# esp32_pwr.net
KiCad netlist of a schematic drawn in EAGLE
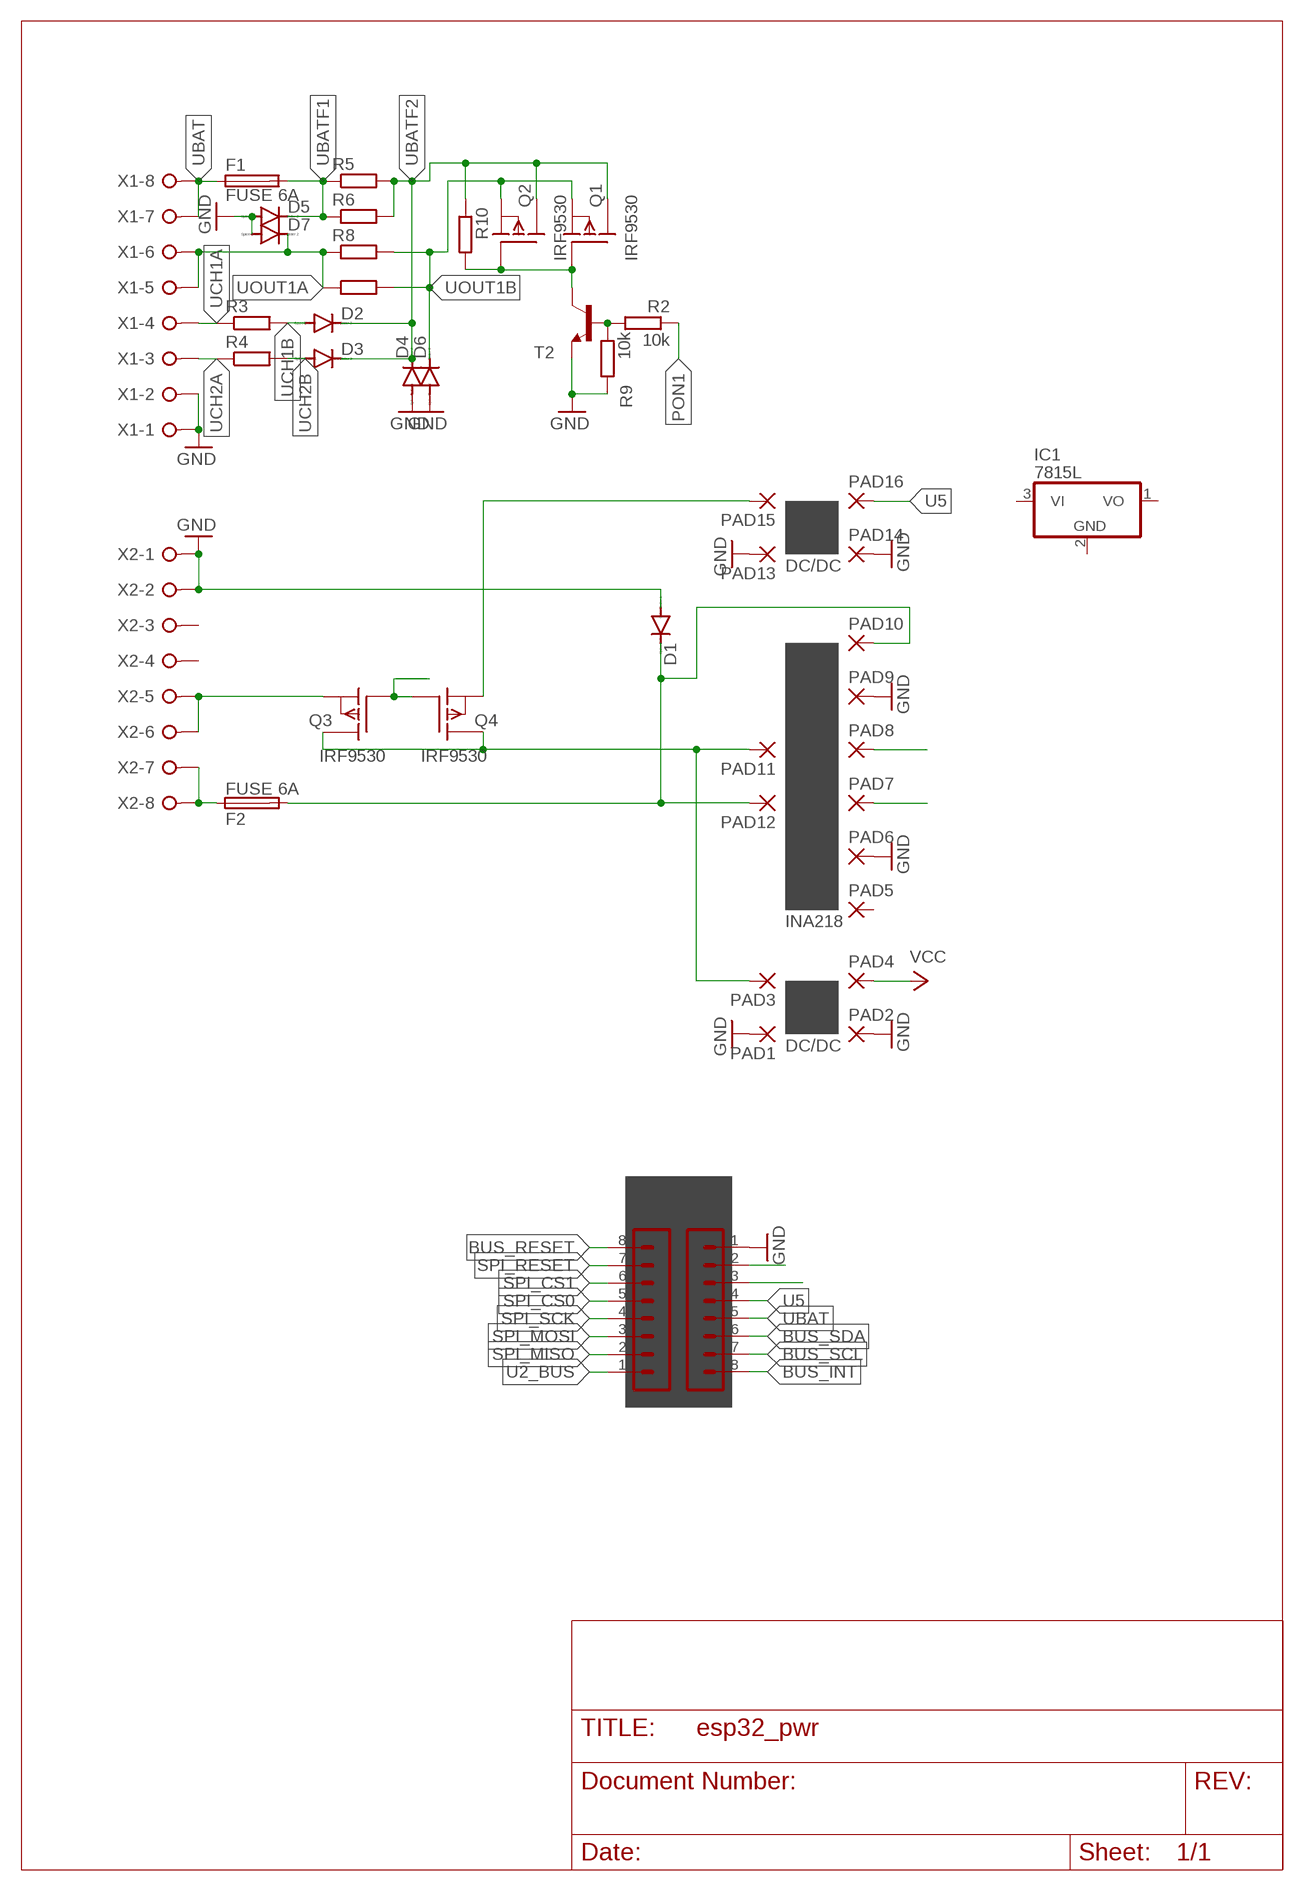
[diagram p0: schematic, sheet 1]

(export (version "E")
  (design (tool "Eeschema 10.0.6"))
  (components
    (comp (ref "D1")
      (value "DIODE-MELF-MLL41")
      (footprint "eagle-import:MELF-MLL41")
      (libsource (lib "eagle-import") (part "DIODE-MELF-MLL41"))
    )
    (comp (ref "D2")
      (value "DIODE-MELF-MLL41")
      (footprint "eagle-import:MELF-MLL41")
      (libsource (lib "eagle-import") (part "DIODE-MELF-MLL41"))
    )
    (comp (ref "D3")
      (value "DIODE-MELF-MLL41")
      (footprint "eagle-import:MELF-MLL41")
      (libsource (lib "eagle-import") (part "DIODE-MELF-MLL41"))
    )
    (comp (ref "D4")
      (value "DIODE-MELF-MLL41")
      (footprint "eagle-import:MELF-MLL41")
      (libsource (lib "eagle-import") (part "DIODE-MELF-MLL41"))
    )
    (comp (ref "D5")
      (value "DIODE-MELF-MLL41")
      (footprint "eagle-import:MELF-MLL41")
      (libsource (lib "eagle-import") (part "DIODE-MELF-MLL41"))
    )
    (comp (ref "D6")
      (value "DIODE-MELF-MLL41")
      (footprint "eagle-import:MELF-MLL41")
      (libsource (lib "eagle-import") (part "DIODE-MELF-MLL41"))
    )
    (comp (ref "D7")
      (value "DIODE-MELF-MLL41")
      (footprint "eagle-import:MELF-MLL41")
      (libsource (lib "eagle-import") (part "DIODE-MELF-MLL41"))
    )
    (comp (ref "F1")
      (value "FUSE 6A")
      (footprint "eagle-import:SH22,5A")
      (libsource (lib "eagle-import") (part "FUSESH22,5A"))
    )
    (comp (ref "F2")
      (value "FUSE 6A")
      (footprint "eagle-import:SH22,5A")
      (libsource (lib "eagle-import") (part "FUSESH22,5A"))
    )
    (comp (ref "IC1")
      (value "7815L")
      (footprint "eagle-import:TO92")
      (libsource (lib "eagle-import") (part "78L15"))
    )
    (comp (ref "L")
      (value "MA08-1")
      (footprint "eagle-import:MA08-1")
      (libsource (lib "eagle-import") (part "MA08-1"))
    )
    (comp (ref "PAD1")
      (value "2,15/1,0")
      (footprint "eagle-import:2,15_1,0")
      (libsource (lib "eagle-import") (part "2,15/1,0"))
    )
    (comp (ref "PAD2")
      (value "2,15/1,0")
      (footprint "eagle-import:2,15_1,0")
      (libsource (lib "eagle-import") (part "2,15/1,0"))
    )
    (comp (ref "PAD3")
      (value "2,15/1,0")
      (footprint "eagle-import:2,15_1,0")
      (libsource (lib "eagle-import") (part "2,15/1,0"))
    )
    (comp (ref "PAD4")
      (value "2,15/1,0")
      (footprint "eagle-import:2,15_1,0")
      (libsource (lib "eagle-import") (part "2,15/1,0"))
    )
    (comp (ref "PAD5")
      (value "2,15/1,0")
      (footprint "eagle-import:2,15_1,0")
      (libsource (lib "eagle-import") (part "2,15/1,0"))
    )
    (comp (ref "PAD6")
      (value "2,15/1,0")
      (footprint "eagle-import:2,15_1,0")
      (libsource (lib "eagle-import") (part "2,15/1,0"))
    )
    (comp (ref "PAD7")
      (value "2,15/1,0")
      (footprint "eagle-import:2,15_1,0")
      (libsource (lib "eagle-import") (part "2,15/1,0"))
    )
    (comp (ref "PAD8")
      (value "2,15/1,0")
      (footprint "eagle-import:2,15_1,0")
      (libsource (lib "eagle-import") (part "2,15/1,0"))
    )
    (comp (ref "PAD9")
      (value "2,15/1,0")
      (footprint "eagle-import:2,15_1,0")
      (libsource (lib "eagle-import") (part "2,15/1,0"))
    )
    (comp (ref "PAD10")
      (value "2,15/1,0")
      (footprint "eagle-import:2,15_1,0")
      (libsource (lib "eagle-import") (part "2,15/1,0"))
    )
    (comp (ref "PAD11")
      (value "2,15/1,0")
      (footprint "eagle-import:2,15_1,0")
      (libsource (lib "eagle-import") (part "2,15/1,0"))
    )
    (comp (ref "PAD12")
      (value "2,15/1,0")
      (footprint "eagle-import:2,15_1,0")
      (libsource (lib "eagle-import") (part "2,15/1,0"))
    )
    (comp (ref "PAD13")
      (value "2,15/1,0")
      (footprint "eagle-import:2,15_1,0")
      (libsource (lib "eagle-import") (part "2,15/1,0"))
    )
    (comp (ref "PAD14")
      (value "2,15/1,0")
      (footprint "eagle-import:2,15_1,0")
      (libsource (lib "eagle-import") (part "2,15/1,0"))
    )
    (comp (ref "PAD15")
      (value "2,15/1,0")
      (footprint "eagle-import:2,15_1,0")
      (libsource (lib "eagle-import") (part "2,15/1,0"))
    )
    (comp (ref "PAD16")
      (value "2,15/1,0")
      (footprint "eagle-import:2,15_1,0")
      (libsource (lib "eagle-import") (part "2,15/1,0"))
    )
    (comp (ref "Q1")
      (value "IRF9530")
      (footprint "eagle-import:TO220")
      (libsource (lib "eagle-import") (part "IRF9530"))
    )
    (comp (ref "Q2")
      (value "IRF9530")
      (footprint "eagle-import:TO220")
      (libsource (lib "eagle-import") (part "IRF9530"))
    )
    (comp (ref "Q3")
      (value "IRF9530")
      (footprint "eagle-import:TO220")
      (libsource (lib "eagle-import") (part "IRF9530"))
    )
    (comp (ref "Q4")
      (value "IRF9530")
      (footprint "eagle-import:TO220")
      (libsource (lib "eagle-import") (part "IRF9530"))
    )
    (comp (ref "R")
      (value "MA08-1")
      (footprint "eagle-import:MA08-1")
      (libsource (lib "eagle-import") (part "MA08-1"))
    )
    (comp (ref "R2")
      (value "10k")
      (footprint "eagle-import:R0805")
      (libsource (lib "eagle-import") (part "R-EU_R0805"))
    )
    (comp (ref "R3")
      (value "R-EU_R2512")
      (footprint "eagle-import:R2512")
      (libsource (lib "eagle-import") (part "rcl_334_R-EU_R2512"))
    )
    (comp (ref "R4")
      (value "R-EU_R2512")
      (footprint "eagle-import:R2512")
      (libsource (lib "eagle-import") (part "rcl_334_R-EU_R2512"))
    )
    (comp (ref "R5")
      (value "R-EU_R2512")
      (footprint "eagle-import:R2512")
      (libsource (lib "eagle-import") (part "rcl_334_R-EU_R2512"))
    )
    (comp (ref "R6")
      (value "R-EU_R2512")
      (footprint "eagle-import:R2512")
      (libsource (lib "eagle-import") (part "rcl_334_R-EU_R2512"))
    )
    (comp (ref "R7")
      (value "R-EU_R2512")
      (footprint "eagle-import:R2512")
      (libsource (lib "eagle-import") (part "rcl_334_R-EU_R2512"))
    )
    (comp (ref "R8")
      (value "R-EU_R2512")
      (footprint "eagle-import:R2512")
      (libsource (lib "eagle-import") (part "rcl_334_R-EU_R2512"))
    )
    (comp (ref "R9")
      (value "10k")
      (footprint "eagle-import:R0805")
      (libsource (lib "eagle-import") (part "R-EU_R0805"))
    )
    (comp (ref "R10")
      (value "R-EU_R0805")
      (footprint "eagle-import:R0805")
      (libsource (lib "eagle-import") (part "rcl_334_R-EU_R0805"))
    )
    (comp (ref "T2")
      (value "BC817-16-NPN-SOT23-BEC")
      (footprint "eagle-import:SOT23-BEC")
      (libsource (lib "eagle-import") (part "-NPN-SOT23-BECBC817-16"))
    )
    (comp (ref "X1")
      (value "W237-08P")
      (footprint "eagle-import:W237-8P")
      (libsource (lib "eagle-import") (part "W237-08P"))
    )
    (comp (ref "X2")
      (value "W237-08P")
      (footprint "eagle-import:W237-8P")
      (libsource (lib "eagle-import") (part "W237-08P"))
    )
  )
  (nets
    (net (code "1") (name "BUS_INT") (class "Default")
      (node (ref "R") (pin "8") (pinfunction "8_8") (pintype "passive"))
    )
    (net (code "2") (name "BUS_RESET") (class "Default")
      (node (ref "L") (pin "8") (pinfunction "8_8") (pintype "passive"))
    )
    (net (code "3") (name "BUS_SCL") (class "Default")
      (node (ref "R") (pin "7") (pinfunction "7_7") (pintype "passive"))
    )
    (net (code "4") (name "BUS_SDA") (class "Default")
      (node (ref "R") (pin "6") (pinfunction "6_6") (pintype "passive"))
    )
    (net (code "5") (name "GND") (class "Default")
      (node (ref "D1") (pin "A") (pinfunction "A_A") (pintype "passive"))
      (node (ref "D4") (pin "A") (pinfunction "A_A") (pintype "passive"))
      (node (ref "D5") (pin "A") (pinfunction "A_A") (pintype "passive"))
      (node (ref "D6") (pin "A") (pinfunction "A_A") (pintype "passive"))
      (node (ref "D7") (pin "A") (pinfunction "A_A") (pintype "passive"))
      (node (ref "PAD1") (pin "1") (pinfunction "P_1") (pintype "passive"))
      (node (ref "PAD13") (pin "1") (pinfunction "P_1") (pintype "passive"))
      (node (ref "PAD14") (pin "1") (pinfunction "P_1") (pintype "passive"))
      (node (ref "PAD2") (pin "1") (pinfunction "P_1") (pintype "passive"))
      (node (ref "PAD6") (pin "1") (pinfunction "P_1") (pintype "passive"))
      (node (ref "PAD9") (pin "1") (pinfunction "P_1") (pintype "passive"))
      (node (ref "R") (pin "1") (pinfunction "1_1") (pintype "passive"))
      (node (ref "R9") (pin "2") (pinfunction "2_2") (pintype "passive"))
      (node (ref "T2") (pin "E") (pinfunction "E_E") (pintype "passive"))
      (node (ref "X1") (pin "1") (pinfunction "KL_1") (pintype "passive"))
      (node (ref "X1") (pin "2") (pinfunction "KL_2") (pintype "passive"))
      (node (ref "X2") (pin "1") (pinfunction "KL_1") (pintype "passive"))
      (node (ref "X2") (pin "2") (pinfunction "KL_2") (pintype "passive"))
    )
    (net (code "6") (name "Net-(PAD10-P)") (class "Default")
      (node (ref "D1") (pin "C") (pinfunction "C_C") (pintype "passive"))
      (node (ref "F2") (pin "2") (pinfunction "2_2") (pintype "passive"))
      (node (ref "PAD10") (pin "1") (pinfunction "P_1") (pintype "passive"))
      (node (ref "PAD12") (pin "1") (pinfunction "P_1") (pintype "passive"))
    )
    (net (code "7") (name "Net-(PAD11-P)") (class "Default")
      (node (ref "PAD11") (pin "1") (pinfunction "P_1") (pintype "passive"))
      (node (ref "PAD3") (pin "1") (pinfunction "P_1") (pintype "passive"))
      (node (ref "Q3") (pin "2") (pinfunction "D_2") (pintype "passive"))
      (node (ref "Q4") (pin "2") (pinfunction "D_2") (pintype "passive"))
    )
    (net (code "8") (name "Net-(PAD15-P)") (class "Default")
      (node (ref "PAD15") (pin "1") (pinfunction "P_1") (pintype "passive"))
      (node (ref "Q4") (pin "3") (pinfunction "S_3") (pintype "passive"))
    )
    (net (code "9") (name "Net-(Q1-G)") (class "Default")
      (node (ref "Q1") (pin "1") (pinfunction "G_1") (pintype "passive"))
      (node (ref "Q2") (pin "1") (pinfunction "G_1") (pintype "passive"))
      (node (ref "R10") (pin "2") (pinfunction "2_2") (pintype "passive"))
      (node (ref "T2") (pin "C") (pinfunction "C_C") (pintype "passive"))
    )
    (net (code "10") (name "Net-(Q3-G)") (class "Default")
      (node (ref "Q3") (pin "1") (pinfunction "G_1") (pintype "passive"))
      (node (ref "Q4") (pin "1") (pinfunction "G_1") (pintype "passive"))
    )
    (net (code "11") (name "Net-(Q3-S)") (class "Default")
      (node (ref "Q3") (pin "3") (pinfunction "S_3") (pintype "passive"))
      (node (ref "X2") (pin "5") (pinfunction "KL_5") (pintype "passive"))
      (node (ref "X2") (pin "6") (pinfunction "KL_6") (pintype "passive"))
    )
    (net (code "12") (name "Net-(R2-Pad2)") (class "Default")
      (node (ref "R2") (pin "2") (pinfunction "2_2") (pintype "passive"))
      (node (ref "R9") (pin "1") (pinfunction "1_1") (pintype "passive"))
      (node (ref "T2") (pin "B") (pinfunction "B_B") (pintype "passive"))
    )
    (net (code "13") (name "Net-(X2G-KL)") (class "Default")
      (node (ref "F2") (pin "1") (pinfunction "1_1") (pintype "passive"))
      (node (ref "X2") (pin "7") (pinfunction "KL_7") (pintype "passive"))
      (node (ref "X2") (pin "8") (pinfunction "KL_8") (pintype "passive"))
    )
    (net (code "14") (name "PON1") (class "Default")
      (node (ref "R2") (pin "1") (pinfunction "1_1") (pintype "passive"))
    )
    (net (code "15") (name "SPI_CS0") (class "Default")
      (node (ref "L") (pin "5") (pinfunction "5_5") (pintype "passive"))
    )
    (net (code "16") (name "SPI_CS1") (class "Default")
      (node (ref "L") (pin "6") (pinfunction "6_6") (pintype "passive"))
    )
    (net (code "17") (name "SPI_MISO") (class "Default")
      (node (ref "L") (pin "2") (pinfunction "2_2") (pintype "passive"))
    )
    (net (code "18") (name "SPI_MOSI") (class "Default")
      (node (ref "L") (pin "3") (pinfunction "3_3") (pintype "passive"))
    )
    (net (code "19") (name "SPI_RESET") (class "Default")
      (node (ref "L") (pin "7") (pinfunction "7_7") (pintype "passive"))
    )
    (net (code "20") (name "SPI_SCK") (class "Default")
      (node (ref "L") (pin "4") (pinfunction "4_4") (pintype "passive"))
    )
    (net (code "21") (name "U2_BUS") (class "Default")
      (node (ref "L") (pin "1") (pinfunction "1_1") (pintype "passive"))
    )
    (net (code "22") (name "U5") (class "Default")
      (node (ref "PAD16") (pin "1") (pinfunction "P_1") (pintype "passive"))
      (node (ref "R") (pin "4") (pinfunction "4_4") (pintype "passive"))
    )
    (net (code "23") (name "UBAT") (class "Default")
      (node (ref "F1") (pin "1") (pinfunction "1_1") (pintype "passive"))
      (node (ref "R") (pin "5") (pinfunction "5_5") (pintype "passive"))
      (node (ref "X1") (pin "7") (pinfunction "KL_7") (pintype "passive"))
      (node (ref "X1") (pin "8") (pinfunction "KL_8") (pintype "passive"))
    )
    (net (code "24") (name "UBATF1") (class "Default")
      (node (ref "D5") (pin "C") (pinfunction "C_C") (pintype "passive"))
      (node (ref "F1") (pin "2") (pinfunction "2_2") (pintype "passive"))
      (node (ref "R5") (pin "1") (pinfunction "1_1") (pintype "passive"))
      (node (ref "R6") (pin "1") (pinfunction "1_1") (pintype "passive"))
    )
    (net (code "25") (name "UBATF2") (class "Default")
      (node (ref "D2") (pin "C") (pinfunction "C_C") (pintype "passive"))
      (node (ref "D3") (pin "C") (pinfunction "C_C") (pintype "passive"))
      (node (ref "D4") (pin "C") (pinfunction "C_C") (pintype "passive"))
      (node (ref "Q1") (pin "2") (pinfunction "D_2") (pintype "passive"))
      (node (ref "Q2") (pin "2") (pinfunction "D_2") (pintype "passive"))
      (node (ref "R10") (pin "1") (pinfunction "1_1") (pintype "passive"))
      (node (ref "R5") (pin "2") (pinfunction "2_2") (pintype "passive"))
      (node (ref "R6") (pin "2") (pinfunction "2_2") (pintype "passive"))
    )
    (net (code "26") (name "UCH1A") (class "Default")
      (node (ref "R3") (pin "1") (pinfunction "1_1") (pintype "passive"))
      (node (ref "X1") (pin "4") (pinfunction "KL_4") (pintype "passive"))
    )
    (net (code "27") (name "UCH1B") (class "Default")
      (node (ref "D2") (pin "A") (pinfunction "A_A") (pintype "passive"))
      (node (ref "R3") (pin "2") (pinfunction "2_2") (pintype "passive"))
    )
    (net (code "28") (name "UCH2A") (class "Default")
      (node (ref "R4") (pin "1") (pinfunction "1_1") (pintype "passive"))
      (node (ref "X1") (pin "3") (pinfunction "KL_3") (pintype "passive"))
    )
    (net (code "29") (name "UCH2B") (class "Default")
      (node (ref "D3") (pin "A") (pinfunction "A_A") (pintype "passive"))
      (node (ref "R4") (pin "2") (pinfunction "2_2") (pintype "passive"))
    )
    (net (code "30") (name "UOUT1A") (class "Default")
      (node (ref "D7") (pin "C") (pinfunction "C_C") (pintype "passive"))
      (node (ref "R7") (pin "1") (pinfunction "1_1") (pintype "passive"))
      (node (ref "R8") (pin "1") (pinfunction "1_1") (pintype "passive"))
      (node (ref "X1") (pin "5") (pinfunction "KL_5") (pintype "passive"))
      (node (ref "X1") (pin "6") (pinfunction "KL_6") (pintype "passive"))
    )
    (net (code "31") (name "UOUT1B") (class "Default")
      (node (ref "D6") (pin "C") (pinfunction "C_C") (pintype "passive"))
      (node (ref "Q1") (pin "3") (pinfunction "S_3") (pintype "passive"))
      (node (ref "Q2") (pin "3") (pinfunction "S_3") (pintype "passive"))
      (node (ref "R7") (pin "2") (pinfunction "2_2") (pintype "passive"))
      (node (ref "R8") (pin "2") (pinfunction "2_2") (pintype "passive"))
    )
    (net (code "32") (name "VCC") (class "Default")
      (node (ref "PAD4") (pin "1") (pinfunction "P_1") (pintype "passive"))
    )
    (net (code "33") (name "unconnected-(IC1-GND-Pad2)") (class "Default")
      (node (ref "IC1") (pin "2") (pinfunction "GND_2") (pintype "passive"))
    )
    (net (code "34") (name "unconnected-(IC1-VI-Pad3)") (class "Default")
      (node (ref "IC1") (pin "3") (pinfunction "VI_3") (pintype "input"))
    )
    (net (code "35") (name "unconnected-(IC1-VO-Pad1)") (class "Default")
      (node (ref "IC1") (pin "1") (pinfunction "VO_1") (pintype "passive"))
    )
    (net (code "36") (name "unconnected-(PAD5-P-Pad1)") (class "Default")
      (node (ref "PAD5") (pin "1") (pinfunction "P_1") (pintype "passive"))
    )
    (net (code "37") (name "unconnected-(PAD7-P-Pad1)") (class "Default")
      (node (ref "PAD7") (pin "1") (pinfunction "P_1") (pintype "passive"))
    )
    (net (code "38") (name "unconnected-(PAD8-P-Pad1)") (class "Default")
      (node (ref "PAD8") (pin "1") (pinfunction "P_1") (pintype "passive"))
    )
    (net (code "39") (name "unconnected-(R-Pad2)") (class "Default")
      (node (ref "R") (pin "2") (pinfunction "2_2") (pintype "passive"))
    )
    (net (code "40") (name "unconnected-(R-Pad3)") (class "Default")
      (node (ref "R") (pin "3") (pinfunction "3_3") (pintype "passive"))
    )
    (net (code "41") (name "unconnected-(X2C-KL-Pad3)") (class "Default")
      (node (ref "X2") (pin "3") (pinfunction "KL_3") (pintype "passive"))
    )
    (net (code "42") (name "unconnected-(X2D-KL-Pad4)") (class "Default")
      (node (ref "X2") (pin "4") (pinfunction "KL_4") (pintype "passive"))
    )
  )
)
